# headstageNano.net
KiCad netlist of a schematic drawn in EAGLE
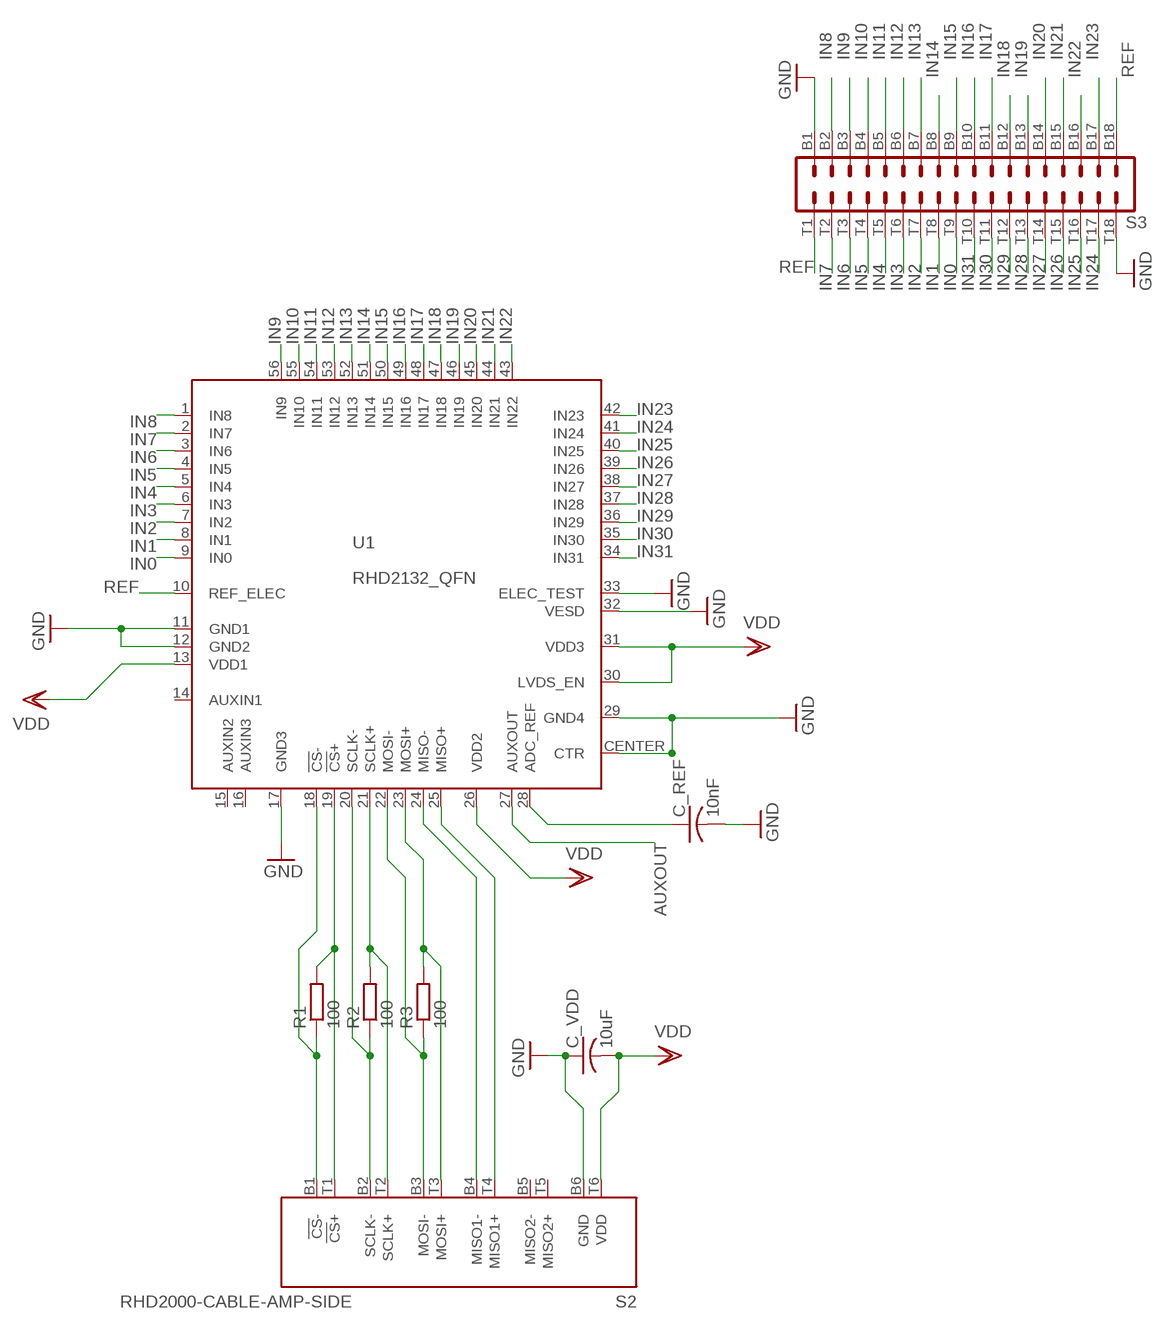
[diagram p0: schematic, sheet 1]

(export (version "E")
  (design (tool "Eeschema 10.0.6"))
  (components
    (comp (ref "C_REF")
      (value "10nF")
      (footprint "eagle-import:C0402K")
      (libsource (lib "eagle-import") (part "C-USC0402K"))
    )
    (comp (ref "C_VDD")
      (value "10uF")
      (footprint "eagle-import:C0402K")
      (libsource (lib "eagle-import") (part "C-USC0402K"))
    )
    (comp (ref "R1")
      (value "100")
      (footprint "eagle-import:R0402")
      (libsource (lib "eagle-import") (part "R-EU_R0402"))
    )
    (comp (ref "R2")
      (value "100")
      (footprint "eagle-import:R0402")
      (libsource (lib "eagle-import") (part "R-EU_R0402"))
    )
    (comp (ref "R3")
      (value "100")
      (footprint "eagle-import:R0402")
      (libsource (lib "eagle-import") (part "R-EU_R0402"))
    )
    (comp (ref "S2")
      (value "RHD2000-CABLE-AMP-SIDE")
      (footprint "eagle-import:OMNETICS_PZN-12-AA")
      (libsource (lib "eagle-import") (part "RHD2000-CABLE-AMP-SIDE"))
    )
    (comp (ref "S3")
      (value "OMNETICS_A79025")
      (footprint "eagle-import:OMNETICS_A79025")
      (libsource (lib "eagle-import") (part "OMNETICS_A79025"))
    )
    (comp (ref "U1")
      (value "RHD2132_QFN")
      (footprint "eagle-import:QFN56_8_X_8_LARGE")
      (libsource (lib "eagle-import") (part "RHD2132_QFN"))
    )
  )
  (nets
    (net (code "1") (name "/AUXOUT") (class "Default")
      (node (ref "U1") (pin "27") (pinfunction "AUXOUT_27") (pintype "tri_state"))
    )
    (net (code "2") (name "/IN0") (class "Default")
      (node (ref "S3") (pin "T9") (pinfunction "T9_T9") (pintype "passive"))
      (node (ref "U1") (pin "9") (pinfunction "IN0_9") (pintype "input"))
    )
    (net (code "3") (name "/IN1") (class "Default")
      (node (ref "S3") (pin "T8") (pinfunction "T8_T8") (pintype "passive"))
      (node (ref "U1") (pin "8") (pinfunction "IN1_8") (pintype "input"))
    )
    (net (code "4") (name "/IN2") (class "Default")
      (node (ref "S3") (pin "T7") (pinfunction "T7_T7") (pintype "passive"))
      (node (ref "U1") (pin "7") (pinfunction "IN2_7") (pintype "input"))
    )
    (net (code "5") (name "/IN3") (class "Default")
      (node (ref "S3") (pin "T6") (pinfunction "T6_T6") (pintype "passive"))
      (node (ref "U1") (pin "6") (pinfunction "IN3_6") (pintype "input"))
    )
    (net (code "6") (name "/IN4") (class "Default")
      (node (ref "S3") (pin "T5") (pinfunction "T5_T5") (pintype "passive"))
      (node (ref "U1") (pin "5") (pinfunction "IN4_5") (pintype "input"))
    )
    (net (code "7") (name "/IN5") (class "Default")
      (node (ref "S3") (pin "T4") (pinfunction "T4_T4") (pintype "passive"))
      (node (ref "U1") (pin "4") (pinfunction "IN5_4") (pintype "input"))
    )
    (net (code "8") (name "/IN6") (class "Default")
      (node (ref "S3") (pin "T3") (pinfunction "T3_T3") (pintype "passive"))
      (node (ref "U1") (pin "3") (pinfunction "IN6_3") (pintype "input"))
    )
    (net (code "9") (name "/IN7") (class "Default")
      (node (ref "S3") (pin "T2") (pinfunction "T2_T2") (pintype "passive"))
      (node (ref "U1") (pin "2") (pinfunction "IN7_2") (pintype "input"))
    )
    (net (code "10") (name "/IN8") (class "Default")
      (node (ref "S3") (pin "B2") (pinfunction "B2_B2") (pintype "passive"))
      (node (ref "U1") (pin "1") (pinfunction "IN8_1") (pintype "input"))
    )
    (net (code "11") (name "/IN9") (class "Default")
      (node (ref "S3") (pin "B3") (pinfunction "B3_B3") (pintype "passive"))
      (node (ref "U1") (pin "56") (pinfunction "IN9_56") (pintype "input"))
    )
    (net (code "12") (name "/IN10") (class "Default")
      (node (ref "S3") (pin "B4") (pinfunction "B4_B4") (pintype "passive"))
      (node (ref "U1") (pin "55") (pinfunction "IN10_55") (pintype "input"))
    )
    (net (code "13") (name "/IN11") (class "Default")
      (node (ref "S3") (pin "B5") (pinfunction "B5_B5") (pintype "passive"))
      (node (ref "U1") (pin "54") (pinfunction "IN11_54") (pintype "input"))
    )
    (net (code "14") (name "/IN12") (class "Default")
      (node (ref "S3") (pin "B6") (pinfunction "B6_B6") (pintype "passive"))
      (node (ref "U1") (pin "53") (pinfunction "IN12_53") (pintype "input"))
    )
    (net (code "15") (name "/IN13") (class "Default")
      (node (ref "S3") (pin "B7") (pinfunction "B7_B7") (pintype "passive"))
      (node (ref "U1") (pin "52") (pinfunction "IN13_52") (pintype "input"))
    )
    (net (code "16") (name "/IN14") (class "Default")
      (node (ref "S3") (pin "B8") (pinfunction "B8_B8") (pintype "passive"))
      (node (ref "U1") (pin "51") (pinfunction "IN14_51") (pintype "input"))
    )
    (net (code "17") (name "/IN15") (class "Default")
      (node (ref "S3") (pin "B9") (pinfunction "B9_B9") (pintype "passive"))
      (node (ref "U1") (pin "50") (pinfunction "IN15_50") (pintype "input"))
    )
    (net (code "18") (name "/IN16") (class "Default")
      (node (ref "S3") (pin "B10") (pinfunction "B10_B10") (pintype "passive"))
      (node (ref "U1") (pin "49") (pinfunction "IN16_49") (pintype "input"))
    )
    (net (code "19") (name "/IN17") (class "Default")
      (node (ref "S3") (pin "B11") (pinfunction "B11_B11") (pintype "passive"))
      (node (ref "U1") (pin "48") (pinfunction "IN17_48") (pintype "input"))
    )
    (net (code "20") (name "/IN18") (class "Default")
      (node (ref "S3") (pin "B12") (pinfunction "B12_B12") (pintype "passive"))
      (node (ref "U1") (pin "47") (pinfunction "IN18_47") (pintype "input"))
    )
    (net (code "21") (name "/IN19") (class "Default")
      (node (ref "S3") (pin "B13") (pinfunction "B13_B13") (pintype "passive"))
      (node (ref "U1") (pin "46") (pinfunction "IN19_46") (pintype "input"))
    )
    (net (code "22") (name "/IN20") (class "Default")
      (node (ref "S3") (pin "B14") (pinfunction "B14_B14") (pintype "passive"))
      (node (ref "U1") (pin "45") (pinfunction "IN20_45") (pintype "input"))
    )
    (net (code "23") (name "/IN21") (class "Default")
      (node (ref "S3") (pin "B15") (pinfunction "B15_B15") (pintype "passive"))
      (node (ref "U1") (pin "44") (pinfunction "IN21_44") (pintype "input"))
    )
    (net (code "24") (name "/IN22") (class "Default")
      (node (ref "S3") (pin "B16") (pinfunction "B16_B16") (pintype "passive"))
      (node (ref "U1") (pin "43") (pinfunction "IN22_43") (pintype "input"))
    )
    (net (code "25") (name "/IN23") (class "Default")
      (node (ref "S3") (pin "B17") (pinfunction "B17_B17") (pintype "passive"))
      (node (ref "U1") (pin "42") (pinfunction "IN23_42") (pintype "input"))
    )
    (net (code "26") (name "/IN24") (class "Default")
      (node (ref "S3") (pin "T17") (pinfunction "T17_T17") (pintype "passive"))
      (node (ref "U1") (pin "41") (pinfunction "IN24_41") (pintype "input"))
    )
    (net (code "27") (name "/IN25") (class "Default")
      (node (ref "S3") (pin "T16") (pinfunction "T16_T16") (pintype "passive"))
      (node (ref "U1") (pin "40") (pinfunction "IN25_40") (pintype "input"))
    )
    (net (code "28") (name "/IN26") (class "Default")
      (node (ref "S3") (pin "T15") (pinfunction "T15_T15") (pintype "passive"))
      (node (ref "U1") (pin "39") (pinfunction "IN26_39") (pintype "input"))
    )
    (net (code "29") (name "/IN27") (class "Default")
      (node (ref "S3") (pin "T14") (pinfunction "T14_T14") (pintype "passive"))
      (node (ref "U1") (pin "38") (pinfunction "IN27_38") (pintype "input"))
    )
    (net (code "30") (name "/IN28") (class "Default")
      (node (ref "S3") (pin "T13") (pinfunction "T13_T13") (pintype "passive"))
      (node (ref "U1") (pin "37") (pinfunction "IN28_37") (pintype "input"))
    )
    (net (code "31") (name "/IN29") (class "Default")
      (node (ref "S3") (pin "T12") (pinfunction "T12_T12") (pintype "passive"))
      (node (ref "U1") (pin "36") (pinfunction "IN29_36") (pintype "input"))
    )
    (net (code "32") (name "/IN30") (class "Default")
      (node (ref "S3") (pin "T11") (pinfunction "T11_T11") (pintype "passive"))
      (node (ref "U1") (pin "35") (pinfunction "IN30_35") (pintype "input"))
    )
    (net (code "33") (name "/IN31") (class "Default")
      (node (ref "S3") (pin "T10") (pinfunction "T10_T10") (pintype "passive"))
      (node (ref "U1") (pin "34") (pinfunction "IN31_34") (pintype "input"))
    )
    (net (code "34") (name "/REF") (class "Default")
      (node (ref "S3") (pin "B18") (pinfunction "B18_B18") (pintype "passive"))
      (node (ref "S3") (pin "T1") (pinfunction "T1_T1") (pintype "passive"))
      (node (ref "U1") (pin "10") (pinfunction "REF_ELEC_10") (pintype "input"))
    )
    (net (code "35") (name "GND") (class "Default")
      (node (ref "C_REF") (pin "2") (pinfunction "2_2") (pintype "passive"))
      (node (ref "C_VDD") (pin "1") (pinfunction "1_1") (pintype "passive"))
      (node (ref "S2") (pin "B6") (pinfunction "GND_B6") (pintype "power_in"))
      (node (ref "S3") (pin "B1") (pinfunction "B1_B1") (pintype "passive"))
      (node (ref "S3") (pin "T18") (pinfunction "T18_T18") (pintype "passive"))
      (node (ref "U1") (pin "11") (pinfunction "GND1_11") (pintype "power_in"))
      (node (ref "U1") (pin "12") (pinfunction "GND2_12") (pintype "power_in"))
      (node (ref "U1") (pin "17") (pinfunction "GND3_17") (pintype "power_in"))
      (node (ref "U1") (pin "29") (pinfunction "GND4_29") (pintype "power_in"))
      (node (ref "U1") (pin "32") (pinfunction "VESD_32") (pintype "power_in"))
      (node (ref "U1") (pin "33") (pinfunction "ELEC_TEST_33") (pintype "input"))
      (node (ref "U1") (pin "CENTER") (pinfunction "CTR_CENTER") (pintype "power_in"))
    )
    (net (code "36") (name "Net-(S2-MISO1+)") (class "Default")
      (node (ref "S2") (pin "T4") (pinfunction "MISO1+_T4") (pintype "bidirectional"))
      (node (ref "U1") (pin "25") (pinfunction "MISO+_25") (pintype "output"))
    )
    (net (code "37") (name "Net-(S2-MISO1-)") (class "Default")
      (node (ref "S2") (pin "B4") (pinfunction "MISO1-_B4") (pintype "bidirectional"))
      (node (ref "U1") (pin "24") (pinfunction "MISO-_24") (pintype "output"))
    )
    (net (code "38") (name "Net-(S2-MOSI+)") (class "Default")
      (node (ref "R3") (pin "2") (pinfunction "2_2") (pintype "passive"))
      (node (ref "S2") (pin "T3") (pinfunction "MOSI+_T3") (pintype "bidirectional"))
      (node (ref "U1") (pin "23") (pinfunction "MOSI+_23") (pintype "input"))
    )
    (net (code "39") (name "Net-(S2-MOSI-)") (class "Default")
      (node (ref "R3") (pin "1") (pinfunction "1_1") (pintype "passive"))
      (node (ref "S2") (pin "B3") (pinfunction "MOSI-_B3") (pintype "bidirectional"))
      (node (ref "U1") (pin "22") (pinfunction "MOSI-_22") (pintype "input"))
    )
    (net (code "40") (name "Net-(S2-SCLK+)") (class "Default")
      (node (ref "R2") (pin "2") (pinfunction "2_2") (pintype "passive"))
      (node (ref "S2") (pin "T2") (pinfunction "SCLK+_T2") (pintype "bidirectional"))
      (node (ref "U1") (pin "21") (pinfunction "SCLK+_21") (pintype "input"))
    )
    (net (code "41") (name "Net-(S2-SCLK-)") (class "Default")
      (node (ref "R2") (pin "1") (pinfunction "1_1") (pintype "passive"))
      (node (ref "S2") (pin "B2") (pinfunction "SCLK-_B2") (pintype "bidirectional"))
      (node (ref "U1") (pin "20") (pinfunction "SCLK-_20") (pintype "input"))
    )
    (net (code "42") (name "Net-(S2-~{CS}+)") (class "Default")
      (node (ref "R1") (pin "2") (pinfunction "2_2") (pintype "passive"))
      (node (ref "S2") (pin "T1") (pinfunction "~{CS}+_T1") (pintype "bidirectional"))
      (node (ref "U1") (pin "19") (pinfunction "~{CS}+_19") (pintype "input"))
    )
    (net (code "43") (name "Net-(S2-~{CS}-)") (class "Default")
      (node (ref "R1") (pin "1") (pinfunction "1_1") (pintype "passive"))
      (node (ref "S2") (pin "B1") (pinfunction "~{CS}-_B1") (pintype "bidirectional"))
      (node (ref "U1") (pin "18") (pinfunction "~{CS}-_18") (pintype "input"))
    )
    (net (code "44") (name "Net-(U1-ADC_REF)") (class "Default")
      (node (ref "C_REF") (pin "1") (pinfunction "1_1") (pintype "passive"))
      (node (ref "U1") (pin "28") (pinfunction "ADC_REF_28") (pintype "passive"))
    )
    (net (code "45") (name "VDD") (class "Default")
      (node (ref "C_VDD") (pin "2") (pinfunction "2_2") (pintype "passive"))
      (node (ref "S2") (pin "T6") (pinfunction "VDD_T6") (pintype "bidirectional"))
      (node (ref "U1") (pin "13") (pinfunction "VDD1_13") (pintype "power_in"))
      (node (ref "U1") (pin "26") (pinfunction "VDD2_26") (pintype "power_in"))
      (node (ref "U1") (pin "30") (pinfunction "LVDS_EN_30") (pintype "input"))
      (node (ref "U1") (pin "31") (pinfunction "VDD3_31") (pintype "power_in"))
    )
    (net (code "46") (name "unconnected-(S2-MISO2+-PadT5)") (class "Default")
      (node (ref "S2") (pin "T5") (pinfunction "MISO2+_T5") (pintype "bidirectional"))
    )
    (net (code "47") (name "unconnected-(S2-MISO2--PadB5)") (class "Default")
      (node (ref "S2") (pin "B5") (pinfunction "MISO2-_B5") (pintype "bidirectional"))
    )
    (net (code "48") (name "unconnected-(U1-AUXIN1-Pad14)") (class "Default")
      (node (ref "U1") (pin "14") (pinfunction "AUXIN1_14") (pintype "input"))
    )
    (net (code "49") (name "unconnected-(U1-AUXIN2-Pad15)") (class "Default")
      (node (ref "U1") (pin "15") (pinfunction "AUXIN2_15") (pintype "input"))
    )
    (net (code "50") (name "unconnected-(U1-AUXIN3-Pad16)") (class "Default")
      (node (ref "U1") (pin "16") (pinfunction "AUXIN3_16") (pintype "input"))
    )
  )
)
